# CurrentSens.net
KiCad netlist of a schematic drawn in Altium Designer
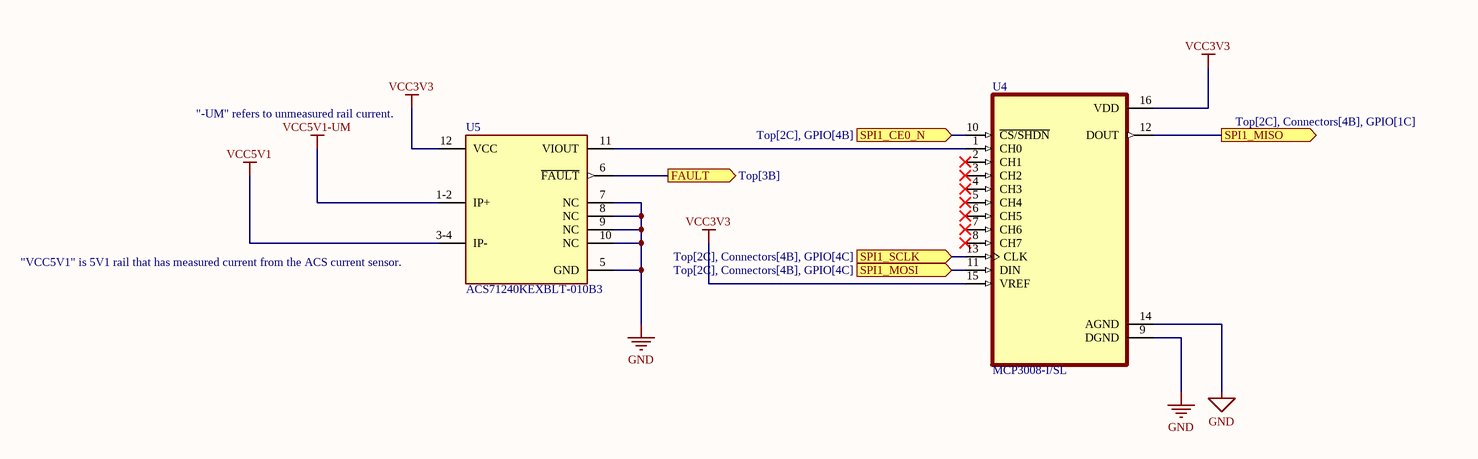
[diagram p0: CurrentSens.SchDoc]

(export (version "E")
  (design (tool "Eeschema 10.0.6"))
  (components
    (comp (ref "U4")
      (value "MCP3008-I/SL")
      (footprint "SOIC127P600X175-16N")
      (description "10 Bit Analog to Digital Converter 4, 8 Input 1 SAR 16-SOIC")
      (fields (field (name "MF") "Microchip"))
      (libsource (lib "MCP3008-I_SL") (part "MCP3008-I/SL"))
    )
    (comp (ref "U5")
      (value "ACS71240KEXBLT-010B3")
      (footprint "FP-EXB-12-MFG")
      (description "AUTOMOTIVE-GRADE, GALVANICALLY I")
      (libsource (lib "Altium Content Vault") (part "f4e867ac890409842fe67e383363e2d"))
    )
  )
  (nets
    (net (code "1") (name "/FAULT") (class "Default")
      (node (ref "U5") (pin "6") (pinfunction "~{FAULT}_6") (pintype "output"))
    )
    (net (code "2") (name "/SPI1_CE0_N") (class "Default")
      (node (ref "U4") (pin "10") (pinfunction "~{CS/SHDN}_10") (pintype "input"))
    )
    (net (code "3") (name "/SPI1_MISO") (class "Default")
      (node (ref "U4") (pin "12") (pinfunction "DOUT_12") (pintype "output"))
    )
    (net (code "4") (name "/SPI1_MOSI") (class "Default")
      (node (ref "U4") (pin "11") (pinfunction "DIN_11") (pintype "input"))
    )
    (net (code "5") (name "/SPI1_SCLK") (class "Default")
      (node (ref "U4") (pin "13") (pinfunction "CLK_13") (pintype "input"))
    )
    (net (code "6") (name "GND") (class "Default")
      (node (ref "U4") (pin "14") (pinfunction "AGND_14") (pintype "power_in"))
      (node (ref "U4") (pin "9") (pinfunction "DGND_9") (pintype "power_in"))
      (node (ref "U5") (pin "10") (pinfunction "NC_10") (pintype "passive"))
      (node (ref "U5") (pin "5") (pinfunction "GND_5") (pintype "power_in"))
      (node (ref "U5") (pin "7") (pinfunction "NC_7") (pintype "passive"))
      (node (ref "U5") (pin "8") (pinfunction "NC_8") (pintype "passive"))
      (node (ref "U5") (pin "9") (pinfunction "NC_9") (pintype "passive"))
    )
    (net (code "7") (name "Net-(U4-CH0)") (class "Default")
      (node (ref "U4") (pin "1") (pinfunction "CH0_1") (pintype "input"))
      (node (ref "U5") (pin "11") (pinfunction "VIOUT_11") (pintype "passive"))
    )
    (net (code "8") (name "VCC3V3") (class "Default")
      (node (ref "U4") (pin "15") (pinfunction "VREF_15") (pintype "input"))
      (node (ref "U4") (pin "16") (pinfunction "VDD_16") (pintype "power_in"))
      (node (ref "U5") (pin "12") (pinfunction "VCC_12") (pintype "power_in"))
    )
    (net (code "9") (name "VCC5V1") (class "Default")
      (node (ref "U5") (pin "3-4") (pinfunction "IP-_3-4") (pintype "passive"))
    )
    (net (code "10") (name "VCC5V1-UM") (class "Default")
      (node (ref "U5") (pin "1-2") (pinfunction "IP+_1-2") (pintype "passive"))
    )
    (net (code "11") (name "unconnected-(U4-CH1-Pad2)") (class "Default")
      (node (ref "U4") (pin "2") (pinfunction "CH1_2") (pintype "input+no_connect"))
    )
    (net (code "12") (name "unconnected-(U4-CH2-Pad3)") (class "Default")
      (node (ref "U4") (pin "3") (pinfunction "CH2_3") (pintype "input+no_connect"))
    )
    (net (code "13") (name "unconnected-(U4-CH3-Pad4)") (class "Default")
      (node (ref "U4") (pin "4") (pinfunction "CH3_4") (pintype "input+no_connect"))
    )
    (net (code "14") (name "unconnected-(U4-CH4-Pad5)") (class "Default")
      (node (ref "U4") (pin "5") (pinfunction "CH4_5") (pintype "input+no_connect"))
    )
    (net (code "15") (name "unconnected-(U4-CH5-Pad6)") (class "Default")
      (node (ref "U4") (pin "6") (pinfunction "CH5_6") (pintype "input+no_connect"))
    )
    (net (code "16") (name "unconnected-(U4-CH6-Pad7)") (class "Default")
      (node (ref "U4") (pin "7") (pinfunction "CH6_7") (pintype "input+no_connect"))
    )
    (net (code "17") (name "unconnected-(U4-CH7-Pad8)") (class "Default")
      (node (ref "U4") (pin "8") (pinfunction "CH7_8") (pintype "input+no_connect"))
    )
  )
)
